# autowatering.net
KiCad netlist of a schematic drawn in Altium Designer
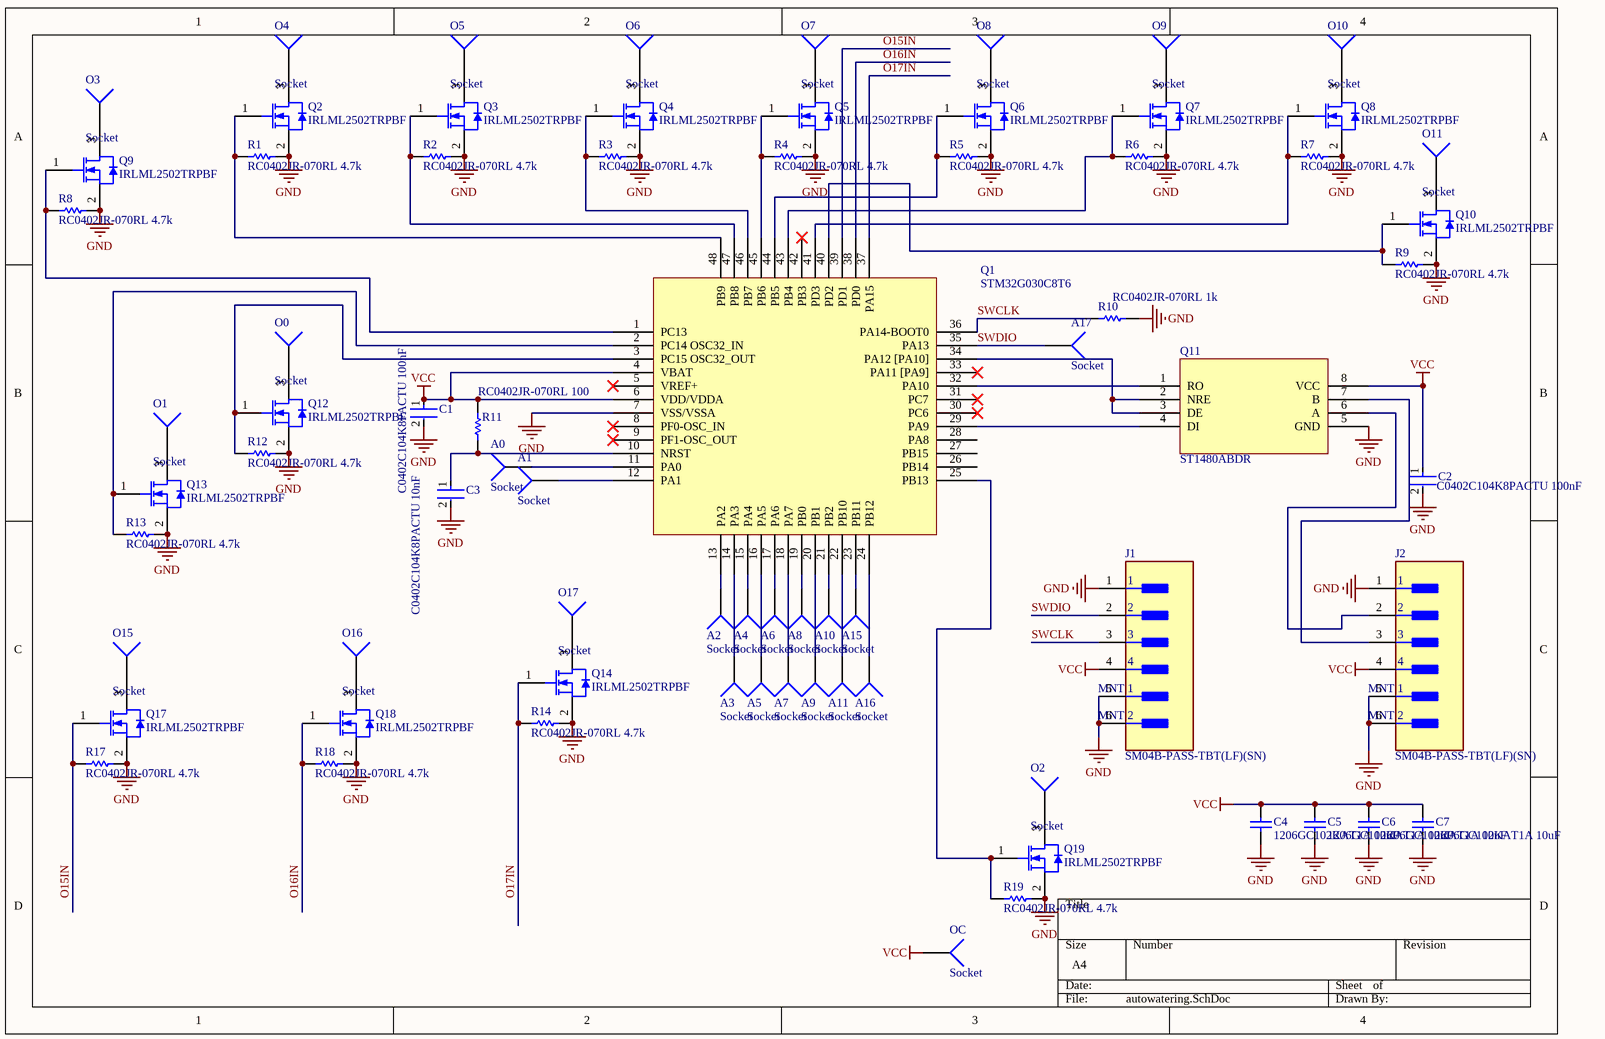
[diagram p0: autowatering.SchDoc]

(export (version "E")
  (design (tool "Eeschema 10.0.6"))
  (components
    (comp (ref "A0")
      (value "Socket")
      (footprint "PIN1")
      (fields (field (name "PUBLISHER") "Altium Limited"))
      (libsource (lib "Miscellaneous Connectors") (part "Socket"))
    )
    (comp (ref "A1")
      (value "Socket")
      (footprint "PIN1")
      (fields (field (name "PUBLISHER") "Altium Limited"))
      (libsource (lib "Miscellaneous Connectors") (part "Socket"))
    )
    (comp (ref "A2")
      (value "Socket")
      (footprint "PIN1")
      (fields (field (name "PUBLISHER") "Altium Limited"))
      (libsource (lib "Miscellaneous Connectors") (part "Socket"))
    )
    (comp (ref "A3")
      (value "Socket")
      (footprint "PIN1")
      (fields (field (name "PUBLISHER") "Altium Limited"))
      (libsource (lib "Miscellaneous Connectors") (part "Socket"))
    )
    (comp (ref "A4")
      (value "Socket")
      (footprint "PIN1")
      (fields (field (name "PUBLISHER") "Altium Limited"))
      (libsource (lib "Miscellaneous Connectors") (part "Socket"))
    )
    (comp (ref "A5")
      (value "Socket")
      (footprint "PIN1")
      (fields (field (name "PUBLISHER") "Altium Limited"))
      (libsource (lib "Miscellaneous Connectors") (part "Socket"))
    )
    (comp (ref "A6")
      (value "Socket")
      (footprint "PIN1")
      (fields (field (name "PUBLISHER") "Altium Limited"))
      (libsource (lib "Miscellaneous Connectors") (part "Socket"))
    )
    (comp (ref "A7")
      (value "Socket")
      (footprint "PIN1")
      (fields (field (name "PUBLISHER") "Altium Limited"))
      (libsource (lib "Miscellaneous Connectors") (part "Socket"))
    )
    (comp (ref "A8")
      (value "Socket")
      (footprint "PIN1")
      (fields (field (name "PUBLISHER") "Altium Limited"))
      (libsource (lib "Miscellaneous Connectors") (part "Socket"))
    )
    (comp (ref "A9")
      (value "Socket")
      (footprint "PIN1")
      (fields (field (name "PUBLISHER") "Altium Limited"))
      (libsource (lib "Miscellaneous Connectors") (part "Socket"))
    )
    (comp (ref "A10")
      (value "Socket")
      (footprint "PIN1")
      (fields (field (name "PUBLISHER") "Altium Limited"))
      (libsource (lib "Miscellaneous Connectors") (part "Socket"))
    )
    (comp (ref "A11")
      (value "Socket")
      (footprint "PIN1")
      (fields (field (name "PUBLISHER") "Altium Limited"))
      (libsource (lib "Miscellaneous Connectors") (part "Socket"))
    )
    (comp (ref "A15")
      (value "Socket")
      (footprint "PIN1")
      (fields (field (name "PUBLISHER") "Altium Limited"))
      (libsource (lib "Miscellaneous Connectors") (part "Socket"))
    )
    (comp (ref "A16")
      (value "Socket")
      (footprint "PIN1")
      (fields (field (name "PUBLISHER") "Altium Limited"))
      (libsource (lib "Miscellaneous Connectors") (part "Socket"))
    )
    (comp (ref "A17")
      (value "Socket")
      (footprint "PIN1")
      (fields (field (name "PUBLISHER") "Altium Limited"))
      (libsource (lib "Miscellaneous Connectors") (part "Socket"))
    )
    (comp (ref "C1")
      (value "C0402C104K8PACTU 100nF")
      (footprint "FP-C0402-BB-MFG")
      (description "CAP CER 0.1UF 10V X5R 0402")
      (fields (field (name "MANUFACTURER") "Kemet") (field (name "TOLERANCE") "0.1"))
      (libsource (lib "Altium Content Vault") (part "b4654b650e69147ec39a6b967a45e02"))
    )
    (comp (ref "C2")
      (value "C0402C104K8PACTU 100nF")
      (footprint "FP-C0402-BB-MFG")
      (description "CAP CER 0.1UF 10V X5R 0402")
      (fields (field (name "MANUFACTURER") "Kemet") (field (name "TOLERANCE") "0.1"))
      (libsource (lib "Altium Content Vault") (part "b4654b650e69147ec39a6b967a45e02"))
    )
    (comp (ref "C3")
      (value "C0402C104K8PACTU 10nF")
      (footprint "FP-C0402-BB-MFG")
      (description "CAP CER 0.1UF 10V X5R 0402")
      (fields (field (name "MANUFACTURER") "Kemet") (field (name "TOLERANCE") "0.1"))
      (libsource (lib "Altium Content Vault") (part "b4654b650e69147ec39a6b967a45e02"))
    )
    (comp (ref "C4")
      (value "1206GC102KAT1A 10uF")
      (footprint "AVX-1206-2_L")
      (description "Chip Capacitor, 1 nF, +/- 10%, -55 to 125 degC, 1206 (3216 Metric), RoHS, Tape and Reel")
      (fields (field (name "TOLERANCE") "10%") (field (name "PARTNUMBER") "1206GC102KAT1A"))
      (libsource (lib "Altium Content Vault") (part "CAP-NP-2"))
    )
    (comp (ref "C5")
      (value "1206GC102KAT1A 10uF")
      (footprint "AVX-1206-2_L")
      (description "Chip Capacitor, 1 nF, +/- 10%, -55 to 125 degC, 1206 (3216 Metric), RoHS, Tape and Reel")
      (fields (field (name "TOLERANCE") "10%") (field (name "PARTNUMBER") "1206GC102KAT1A"))
      (libsource (lib "Altium Content Vault") (part "CAP-NP-2"))
    )
    (comp (ref "C6")
      (value "1206GC102KAT1A 10uF")
      (footprint "AVX-1206-2_L")
      (description "Chip Capacitor, 1 nF, +/- 10%, -55 to 125 degC, 1206 (3216 Metric), RoHS, Tape and Reel")
      (fields (field (name "TOLERANCE") "10%") (field (name "PARTNUMBER") "1206GC102KAT1A"))
      (libsource (lib "Altium Content Vault") (part "CAP-NP-2"))
    )
    (comp (ref "C7")
      (value "1206GC102KAT1A 10uF")
      (footprint "AVX-1206-2_L")
      (description "Chip Capacitor, 1 nF, +/- 10%, -55 to 125 degC, 1206 (3216 Metric), RoHS, Tape and Reel")
      (fields (field (name "TOLERANCE") "10%") (field (name "PARTNUMBER") "1206GC102KAT1A"))
      (libsource (lib "Altium Content Vault") (part "CAP-NP-2"))
    )
    (comp (ref "J1")
      (value "SM04B-PASS-TBT(LF)(SN)")
      (footprint "FP-SM04B-PASS-TBT_LF_SN-MFG")
      (description "CONN HEADER SMD R/A 4POS 2MM")
      (fields
        (field (name "MANUFACTURER") "JST")
        (field (name "OCTOPART") "https://octopart.com/sm04b-pass-tbt%28lf%29%28sn%29-jst-3990422")
      )
      (libsource (lib "Altium Content Vault") (part "8e3688c4b118bffc0dd9b7401e414ba"))
    )
    (comp (ref "J2")
      (value "SM04B-PASS-TBT(LF)(SN)")
      (footprint "FP-SM04B-PASS-TBT_LF_SN-MFG")
      (description "CONN HEADER SMD R/A 4POS 2MM")
      (fields
        (field (name "MANUFACTURER") "JST")
        (field (name "OCTOPART") "https://octopart.com/sm04b-pass-tbt%28lf%29%28sn%29-jst-3990422")
      )
      (libsource (lib "Altium Content Vault") (part "8e3688c4b118bffc0dd9b7401e414ba"))
    )
    (comp (ref "O0")
      (value "Socket")
      (footprint "PIN1")
      (fields (field (name "PUBLISHER") "Altium Limited"))
      (libsource (lib "Miscellaneous Connectors") (part "Socket"))
    )
    (comp (ref "O1")
      (value "Socket")
      (footprint "PIN1")
      (fields (field (name "PUBLISHER") "Altium Limited"))
      (libsource (lib "Miscellaneous Connectors") (part "Socket"))
    )
    (comp (ref "O2")
      (value "Socket")
      (footprint "PIN1")
      (fields (field (name "PUBLISHER") "Altium Limited"))
      (libsource (lib "Miscellaneous Connectors") (part "Socket"))
    )
    (comp (ref "O3")
      (value "Socket")
      (footprint "PIN1")
      (fields (field (name "PUBLISHER") "Altium Limited"))
      (libsource (lib "Miscellaneous Connectors") (part "Socket"))
    )
    (comp (ref "O4")
      (value "Socket")
      (footprint "PIN1")
      (fields (field (name "PUBLISHER") "Altium Limited"))
      (libsource (lib "Miscellaneous Connectors") (part "Socket"))
    )
    (comp (ref "O5")
      (value "Socket")
      (footprint "PIN1")
      (fields (field (name "PUBLISHER") "Altium Limited"))
      (libsource (lib "Miscellaneous Connectors") (part "Socket"))
    )
    (comp (ref "O6")
      (value "Socket")
      (footprint "PIN1")
      (fields (field (name "PUBLISHER") "Altium Limited"))
      (libsource (lib "Miscellaneous Connectors") (part "Socket"))
    )
    (comp (ref "O7")
      (value "Socket")
      (footprint "PIN1")
      (fields (field (name "PUBLISHER") "Altium Limited"))
      (libsource (lib "Miscellaneous Connectors") (part "Socket"))
    )
    (comp (ref "O8")
      (value "Socket")
      (footprint "PIN1")
      (fields (field (name "PUBLISHER") "Altium Limited"))
      (libsource (lib "Miscellaneous Connectors") (part "Socket"))
    )
    (comp (ref "O9")
      (value "Socket")
      (footprint "PIN1")
      (fields (field (name "PUBLISHER") "Altium Limited"))
      (libsource (lib "Miscellaneous Connectors") (part "Socket"))
    )
    (comp (ref "O10")
      (value "Socket")
      (footprint "PIN1")
      (fields (field (name "PUBLISHER") "Altium Limited"))
      (libsource (lib "Miscellaneous Connectors") (part "Socket"))
    )
    (comp (ref "O11")
      (value "Socket")
      (footprint "PIN1")
      (fields (field (name "PUBLISHER") "Altium Limited"))
      (libsource (lib "Miscellaneous Connectors") (part "Socket"))
    )
    (comp (ref "O15")
      (value "Socket")
      (footprint "PIN1")
      (fields (field (name "PUBLISHER") "Altium Limited"))
      (libsource (lib "Miscellaneous Connectors") (part "Socket"))
    )
    (comp (ref "O16")
      (value "Socket")
      (footprint "PIN1")
      (fields (field (name "PUBLISHER") "Altium Limited"))
      (libsource (lib "Miscellaneous Connectors") (part "Socket"))
    )
    (comp (ref "O17")
      (value "Socket")
      (footprint "PIN1")
      (fields (field (name "PUBLISHER") "Altium Limited"))
      (libsource (lib "Miscellaneous Connectors") (part "Socket"))
    )
    (comp (ref "OC")
      (value "Socket")
      (footprint "PIN1")
      (fields (field (name "PUBLISHER") "Altium Limited"))
      (libsource (lib "Miscellaneous Connectors") (part "Socket"))
    )
    (comp (ref "Q1")
      (value "STM32G030C8T6")
      (footprint "LQFP-48")
      (libsource (lib "STM32G030C8T6") (part "STM32G030C8T6"))
    )
    (comp (ref "Q2")
      (value "IRLML2502TRPBF")
      (footprint "INTR-SOT-23-3_V")
      (description "N-Channel HEXFET(R) Power MOSFET, 20 V VDS, +/- 12 V VGS, 4.2 A, 3-Pin SOT23, RoHS, Tape and Reel")
      (fields (field (name "MANUFACTURER") "International Rectifier"))
      (libsource (lib "Altium Content Vault") (part "NEMOS-GSD-3"))
    )
    (comp (ref "Q3")
      (value "IRLML2502TRPBF")
      (footprint "INTR-SOT-23-3_V")
      (description "N-Channel HEXFET(R) Power MOSFET, 20 V VDS, +/- 12 V VGS, 4.2 A, 3-Pin SOT23, RoHS, Tape and Reel")
      (fields (field (name "MANUFACTURER") "International Rectifier"))
      (libsource (lib "Altium Content Vault") (part "NEMOS-GSD-3"))
    )
    (comp (ref "Q4")
      (value "IRLML2502TRPBF")
      (footprint "INTR-SOT-23-3_V")
      (description "N-Channel HEXFET(R) Power MOSFET, 20 V VDS, +/- 12 V VGS, 4.2 A, 3-Pin SOT23, RoHS, Tape and Reel")
      (fields (field (name "MANUFACTURER") "International Rectifier"))
      (libsource (lib "Altium Content Vault") (part "NEMOS-GSD-3"))
    )
    (comp (ref "Q5")
      (value "IRLML2502TRPBF")
      (footprint "INTR-SOT-23-3_V")
      (description "N-Channel HEXFET(R) Power MOSFET, 20 V VDS, +/- 12 V VGS, 4.2 A, 3-Pin SOT23, RoHS, Tape and Reel")
      (fields (field (name "MANUFACTURER") "International Rectifier"))
      (libsource (lib "Altium Content Vault") (part "NEMOS-GSD-3"))
    )
    (comp (ref "Q6")
      (value "IRLML2502TRPBF")
      (footprint "INTR-SOT-23-3_V")
      (description "N-Channel HEXFET(R) Power MOSFET, 20 V VDS, +/- 12 V VGS, 4.2 A, 3-Pin SOT23, RoHS, Tape and Reel")
      (fields (field (name "MANUFACTURER") "International Rectifier"))
      (libsource (lib "Altium Content Vault") (part "NEMOS-GSD-3"))
    )
    (comp (ref "Q7")
      (value "IRLML2502TRPBF")
      (footprint "INTR-SOT-23-3_V")
      (description "N-Channel HEXFET(R) Power MOSFET, 20 V VDS, +/- 12 V VGS, 4.2 A, 3-Pin SOT23, RoHS, Tape and Reel")
      (fields (field (name "MANUFACTURER") "International Rectifier"))
      (libsource (lib "Altium Content Vault") (part "NEMOS-GSD-3"))
    )
    (comp (ref "Q8")
      (value "IRLML2502TRPBF")
      (footprint "INTR-SOT-23-3_V")
      (description "N-Channel HEXFET(R) Power MOSFET, 20 V VDS, +/- 12 V VGS, 4.2 A, 3-Pin SOT23, RoHS, Tape and Reel")
      (fields (field (name "MANUFACTURER") "International Rectifier"))
      (libsource (lib "Altium Content Vault") (part "NEMOS-GSD-3"))
    )
    (comp (ref "Q9")
      (value "IRLML2502TRPBF")
      (footprint "INTR-SOT-23-3_V")
      (description "N-Channel HEXFET(R) Power MOSFET, 20 V VDS, +/- 12 V VGS, 4.2 A, 3-Pin SOT23, RoHS, Tape and Reel")
      (fields (field (name "MANUFACTURER") "International Rectifier"))
      (libsource (lib "Altium Content Vault") (part "NEMOS-GSD-3"))
    )
    (comp (ref "Q10")
      (value "IRLML2502TRPBF")
      (footprint "INTR-SOT-23-3_V")
      (description "N-Channel HEXFET(R) Power MOSFET, 20 V VDS, +/- 12 V VGS, 4.2 A, 3-Pin SOT23, RoHS, Tape and Reel")
      (fields (field (name "MANUFACTURER") "International Rectifier"))
      (libsource (lib "Altium Content Vault") (part "NEMOS-GSD-3"))
    )
    (comp (ref "Q11")
      (value "ST1480ABDR")
      (footprint "8S1_N")
      (libsource (lib "ST1480ABDR") (part "ST1480ABDR"))
    )
    (comp (ref "Q12")
      (value "IRLML2502TRPBF")
      (footprint "INTR-SOT-23-3_V")
      (description "N-Channel HEXFET(R) Power MOSFET, 20 V VDS, +/- 12 V VGS, 4.2 A, 3-Pin SOT23, RoHS, Tape and Reel")
      (fields (field (name "MANUFACTURER") "International Rectifier"))
      (libsource (lib "Altium Content Vault") (part "NEMOS-GSD-3"))
    )
    (comp (ref "Q13")
      (value "IRLML2502TRPBF")
      (footprint "INTR-SOT-23-3_V")
      (description "N-Channel HEXFET(R) Power MOSFET, 20 V VDS, +/- 12 V VGS, 4.2 A, 3-Pin SOT23, RoHS, Tape and Reel")
      (fields (field (name "MANUFACTURER") "International Rectifier"))
      (libsource (lib "Altium Content Vault") (part "NEMOS-GSD-3"))
    )
    (comp (ref "Q14")
      (value "IRLML2502TRPBF")
      (footprint "INTR-SOT-23-3_V")
      (description "N-Channel HEXFET(R) Power MOSFET, 20 V VDS, +/- 12 V VGS, 4.2 A, 3-Pin SOT23, RoHS, Tape and Reel")
      (fields (field (name "MANUFACTURER") "International Rectifier"))
      (libsource (lib "Altium Content Vault") (part "NEMOS-GSD-3"))
    )
    (comp (ref "Q17")
      (value "IRLML2502TRPBF")
      (footprint "INTR-SOT-23-3_V")
      (description "N-Channel HEXFET(R) Power MOSFET, 20 V VDS, +/- 12 V VGS, 4.2 A, 3-Pin SOT23, RoHS, Tape and Reel")
      (fields (field (name "MANUFACTURER") "International Rectifier"))
      (libsource (lib "Altium Content Vault") (part "NEMOS-GSD-3"))
    )
    (comp (ref "Q18")
      (value "IRLML2502TRPBF")
      (footprint "INTR-SOT-23-3_V")
      (description "N-Channel HEXFET(R) Power MOSFET, 20 V VDS, +/- 12 V VGS, 4.2 A, 3-Pin SOT23, RoHS, Tape and Reel")
      (fields (field (name "MANUFACTURER") "International Rectifier"))
      (libsource (lib "Altium Content Vault") (part "NEMOS-GSD-3"))
    )
    (comp (ref "Q19")
      (value "IRLML2502TRPBF")
      (footprint "INTR-SOT-23-3_V")
      (description "N-Channel HEXFET(R) Power MOSFET, 20 V VDS, +/- 12 V VGS, 4.2 A, 3-Pin SOT23, RoHS, Tape and Reel")
      (fields (field (name "MANUFACTURER") "International Rectifier"))
      (libsource (lib "Altium Content Vault") (part "NEMOS-GSD-3"))
    )
    (comp (ref "R1")
      (value "RC0402JR-070RL 4.7k")
      (footprint "RESC1005X40X25NL05T10")
      (fields (field (name "MANUFACTURER") "Yageo / Phycomp") (field (name "PART NUMBER") "RC0402JR-070RL"))
      (libsource (lib "Altium Content Vault") (part "RES"))
    )
    (comp (ref "R2")
      (value "RC0402JR-070RL 4.7k")
      (footprint "RESC1005X40X25NL05T10")
      (fields (field (name "MANUFACTURER") "Yageo / Phycomp") (field (name "PART NUMBER") "RC0402JR-070RL"))
      (libsource (lib "Altium Content Vault") (part "RES"))
    )
    (comp (ref "R3")
      (value "RC0402JR-070RL 4.7k")
      (footprint "RESC1005X40X25NL05T10")
      (fields (field (name "MANUFACTURER") "Yageo / Phycomp") (field (name "PART NUMBER") "RC0402JR-070RL"))
      (libsource (lib "Altium Content Vault") (part "RES"))
    )
    (comp (ref "R4")
      (value "RC0402JR-070RL 4.7k")
      (footprint "RESC1005X40X25NL05T10")
      (fields (field (name "MANUFACTURER") "Yageo / Phycomp") (field (name "PART NUMBER") "RC0402JR-070RL"))
      (libsource (lib "Altium Content Vault") (part "RES"))
    )
    (comp (ref "R5")
      (value "RC0402JR-070RL 4.7k")
      (footprint "RESC1005X40X25NL05T10")
      (fields (field (name "MANUFACTURER") "Yageo / Phycomp") (field (name "PART NUMBER") "RC0402JR-070RL"))
      (libsource (lib "Altium Content Vault") (part "RES"))
    )
    (comp (ref "R6")
      (value "RC0402JR-070RL 4.7k")
      (footprint "RESC1005X40X25NL05T10")
      (fields (field (name "MANUFACTURER") "Yageo / Phycomp") (field (name "PART NUMBER") "RC0402JR-070RL"))
      (libsource (lib "Altium Content Vault") (part "RES"))
    )
    (comp (ref "R7")
      (value "RC0402JR-070RL 4.7k")
      (footprint "RESC1005X40X25NL05T10")
      (fields (field (name "MANUFACTURER") "Yageo / Phycomp") (field (name "PART NUMBER") "RC0402JR-070RL"))
      (libsource (lib "Altium Content Vault") (part "RES"))
    )
    (comp (ref "R8")
      (value "RC0402JR-070RL 4.7k")
      (footprint "RESC1005X40X25NL05T10")
      (fields (field (name "MANUFACTURER") "Yageo / Phycomp") (field (name "PART NUMBER") "RC0402JR-070RL"))
      (libsource (lib "Altium Content Vault") (part "RES"))
    )
    (comp (ref "R9")
      (value "RC0402JR-070RL 4.7k")
      (footprint "RESC1005X40X25NL05T10")
      (fields (field (name "MANUFACTURER") "Yageo / Phycomp") (field (name "PART NUMBER") "RC0402JR-070RL"))
      (libsource (lib "Altium Content Vault") (part "RES"))
    )
    (comp (ref "R10")
      (value "RC0402JR-070RL 1k")
      (footprint "RESC1005X40X25NL05T10")
      (fields (field (name "MANUFACTURER") "Yageo / Phycomp") (field (name "PART NUMBER") "RC0402JR-070RL"))
      (libsource (lib "Altium Content Vault") (part "RES"))
    )
    (comp (ref "R11")
      (value "RC0402JR-070RL 100")
      (footprint "RESC1005X40X25NL05T10")
      (fields (field (name "MANUFACTURER") "Yageo / Phycomp") (field (name "PART NUMBER") "RC0402JR-070RL"))
      (libsource (lib "Altium Content Vault") (part "RES"))
    )
    (comp (ref "R12")
      (value "RC0402JR-070RL 4.7k")
      (footprint "RESC1005X40X25NL05T10")
      (fields (field (name "MANUFACTURER") "Yageo / Phycomp") (field (name "PART NUMBER") "RC0402JR-070RL"))
      (libsource (lib "Altium Content Vault") (part "RES"))
    )
    (comp (ref "R13")
      (value "RC0402JR-070RL 4.7k")
      (footprint "RESC1005X40X25NL05T10")
      (fields (field (name "MANUFACTURER") "Yageo / Phycomp") (field (name "PART NUMBER") "RC0402JR-070RL"))
      (libsource (lib "Altium Content Vault") (part "RES"))
    )
    (comp (ref "R14")
      (value "RC0402JR-070RL 4.7k")
      (footprint "RESC1005X40X25NL05T10")
      (fields (field (name "MANUFACTURER") "Yageo / Phycomp") (field (name "PART NUMBER") "RC0402JR-070RL"))
      (libsource (lib "Altium Content Vault") (part "RES"))
    )
    (comp (ref "R17")
      (value "RC0402JR-070RL 4.7k")
      (footprint "RESC1005X40X25NL05T10")
      (fields (field (name "MANUFACTURER") "Yageo / Phycomp") (field (name "PART NUMBER") "RC0402JR-070RL"))
      (libsource (lib "Altium Content Vault") (part "RES"))
    )
    (comp (ref "R18")
      (value "RC0402JR-070RL 4.7k")
      (footprint "RESC1005X40X25NL05T10")
      (fields (field (name "MANUFACTURER") "Yageo / Phycomp") (field (name "PART NUMBER") "RC0402JR-070RL"))
      (libsource (lib "Altium Content Vault") (part "RES"))
    )
    (comp (ref "R19")
      (value "RC0402JR-070RL 4.7k")
      (footprint "RESC1005X40X25NL05T10")
      (fields (field (name "MANUFACTURER") "Yageo / Phycomp") (field (name "PART NUMBER") "RC0402JR-070RL"))
      (libsource (lib "Altium Content Vault") (part "RES"))
    )
  )
  (nets
    (net (code "1") (name "/O15IN") (class "Default")
      (node (ref "Q1") (pin "39") (pinfunction "PD1_39") (pintype "passive"))
      (node (ref "Q17") (pin "1") (pinfunction "G_1") (pintype "passive"))
      (node (ref "R17") (pin "2") (pinfunction "2_2") (pintype "passive"))
    )
    (net (code "2") (name "/O16IN") (class "Default")
      (node (ref "Q1") (pin "38") (pinfunction "PD0_38") (pintype "passive"))
      (node (ref "Q18") (pin "1") (pinfunction "G_1") (pintype "passive"))
      (node (ref "R18") (pin "2") (pinfunction "2_2") (pintype "passive"))
    )
    (net (code "3") (name "/O17IN") (class "Default")
      (node (ref "Q1") (pin "37") (pinfunction "PA15_37") (pintype "passive"))
      (node (ref "Q14") (pin "1") (pinfunction "G_1") (pintype "passive"))
      (node (ref "R14") (pin "2") (pinfunction "2_2") (pintype "passive"))
    )
    (net (code "4") (name "/SWCLK") (class "Default")
      (node (ref "J1") (pin "3") (pinfunction "3_3") (pintype "passive"))
      (node (ref "Q1") (pin "36") (pinfunction "PA14-BOOT0_36") (pintype "passive"))
      (node (ref "R10") (pin "1") (pinfunction "1_1") (pintype "passive"))
    )
    (net (code "5") (name "/SWDIO") (class "Default")
      (node (ref "A17") (pin "1") (pinfunction "1_1") (pintype "passive"))
      (node (ref "J1") (pin "2") (pinfunction "2_2") (pintype "passive"))
      (node (ref "Q1") (pin "35") (pinfunction "PA13_35") (pintype "passive"))
    )
    (net (code "6") (name "GND") (class "Default")
      (node (ref "C1") (pin "2") (pinfunction "2_2") (pintype "passive"))
      (node (ref "C2") (pin "2") (pinfunction "2_2") (pintype "passive"))
      (node (ref "C3") (pin "2") (pinfunction "2_2") (pintype "passive"))
      (node (ref "C4") (pin "1") (pinfunction "1_1") (pintype "passive"))
      (node (ref "C5") (pin "1") (pinfunction "1_1") (pintype "passive"))
      (node (ref "C6") (pin "1") (pinfunction "1_1") (pintype "passive"))
      (node (ref "C7") (pin "1") (pinfunction "1_1") (pintype "passive"))
      (node (ref "J1") (pin "1") (pinfunction "1_1") (pintype "passive"))
      (node (ref "J1") (pin "5") (pinfunction "MNT_1_5") (pintype "passive"))
      (node (ref "J1") (pin "6") (pinfunction "MNT_2_6") (pintype "passive"))
      (node (ref "J2") (pin "1") (pinfunction "1_1") (pintype "passive"))
      (node (ref "J2") (pin "5") (pinfunction "MNT_1_5") (pintype "passive"))
      (node (ref "J2") (pin "6") (pinfunction "MNT_2_6") (pintype "passive"))
      (node (ref "Q1") (pin "7") (pinfunction "VSS/VSSA_7") (pintype "passive"))
      (node (ref "Q10") (pin "2") (pinfunction "S_2") (pintype "passive"))
      (node (ref "Q11") (pin "5") (pinfunction "GND_5") (pintype "passive"))
      (node (ref "Q12") (pin "2") (pinfunction "S_2") (pintype "passive"))
      (node (ref "Q13") (pin "2") (pinfunction "S_2") (pintype "passive"))
      (node (ref "Q14") (pin "2") (pinfunction "S_2") (pintype "passive"))
      (node (ref "Q17") (pin "2") (pinfunction "S_2") (pintype "passive"))
      (node (ref "Q18") (pin "2") (pinfunction "S_2") (pintype "passive"))
      (node (ref "Q19") (pin "2") (pinfunction "S_2") (pintype "passive"))
      (node (ref "Q2") (pin "2") (pinfunction "S_2") (pintype "passive"))
      (node (ref "Q3") (pin "2") (pinfunction "S_2") (pintype "passive"))
      (node (ref "Q4") (pin "2") (pinfunction "S_2") (pintype "passive"))
      (node (ref "Q5") (pin "2") (pinfunction "S_2") (pintype "passive"))
      (node (ref "Q6") (pin "2") (pinfunction "S_2") (pintype "passive"))
      (node (ref "Q7") (pin "2") (pinfunction "S_2") (pintype "passive"))
      (node (ref "Q8") (pin "2") (pinfunction "S_2") (pintype "passive"))
      (node (ref "Q9") (pin "2") (pinfunction "S_2") (pintype "passive"))
      (node (ref "R1") (pin "1") (pinfunction "1_1") (pintype "passive"))
      (node (ref "R10") (pin "2") (pinfunction "2_2") (pintype "passive"))
      (node (ref "R12") (pin "1") (pinfunction "1_1") (pintype "passive"))
      (node (ref "R13") (pin "1") (pinfunction "1_1") (pintype "passive"))
      (node (ref "R14") (pin "1") (pinfunction "1_1") (pintype "passive"))
      (node (ref "R17") (pin "1") (pinfunction "1_1") (pintype "passive"))
      (node (ref "R18") (pin "1") (pinfunction "1_1") (pintype "passive"))
      (node (ref "R19") (pin "1") (pinfunction "1_1") (pintype "passive"))
      (node (ref "R2") (pin "1") (pinfunction "1_1") (pintype "passive"))
      (node (ref "R3") (pin "1") (pinfunction "1_1") (pintype "passive"))
      (node (ref "R4") (pin "1") (pinfunction "1_1") (pintype "passive"))
      (node (ref "R5") (pin "1") (pinfunction "1_1") (pintype "passive"))
      (node (ref "R6") (pin "1") (pinfunction "1_1") (pintype "passive"))
      (node (ref "R7") (pin "1") (pinfunction "1_1") (pintype "passive"))
      (node (ref "R8") (pin "1") (pinfunction "1_1") (pintype "passive"))
      (node (ref "R9") (pin "1") (pinfunction "1_1") (pintype "passive"))
    )
    (net (code "7") (name "Net-(Q1-NRST)") (class "Default")
      (node (ref "C3") (pin "1") (pinfunction "1_1") (pintype "passive"))
      (node (ref "Q1") (pin "10") (pinfunction "NRST_10") (pintype "passive"))
      (node (ref "R11") (pin "1") (pinfunction "1_1") (pintype "passive"))
    )
    (net (code "8") (name "Net-(Q1-PA0)") (class "Default")
      (node (ref "A0") (pin "1") (pinfunction "1_1") (pintype "passive"))
      (node (ref "Q1") (pin "11") (pinfunction "PA0_11") (pintype "passive"))
    )
    (net (code "9") (name "Net-(Q1-PA1)") (class "Default")
      (node (ref "A1") (pin "1") (pinfunction "1_1") (pintype "passive"))
      (node (ref "Q1") (pin "12") (pinfunction "PA1_12") (pintype "passive"))
    )
    (net (code "10") (name "Net-(Q1-PA2)") (class "Default")
      (node (ref "A2") (pin "1") (pinfunction "1_1") (pintype "passive"))
      (node (ref "Q1") (pin "13") (pinfunction "PA2_13") (pintype "passive"))
    )
    (net (code "11") (name "Net-(Q1-PA3)") (class "Default")
      (node (ref "A3") (pin "1") (pinfunction "1_1") (pintype "passive"))
      (node (ref "Q1") (pin "14") (pinfunction "PA3_14") (pintype "passive"))
    )
    (net (code "12") (name "Net-(Q1-PA4)") (class "Default")
      (node (ref "A4") (pin "1") (pinfunction "1_1") (pintype "passive"))
      (node (ref "Q1") (pin "15") (pinfunction "PA4_15") (pintype "passive"))
    )
    (net (code "13") (name "Net-(Q1-PA5)") (class "Default")
      (node (ref "A5") (pin "1") (pinfunction "1_1") (pintype "passive"))
      (node (ref "Q1") (pin "16") (pinfunction "PA5_16") (pintype "passive"))
    )
    (net (code "14") (name "Net-(Q1-PA6)") (class "Default")
      (node (ref "A6") (pin "1") (pinfunction "1_1") (pintype "passive"))
      (node (ref "Q1") (pin "17") (pinfunction "PA6_17") (pintype "passive"))
    )
    (net (code "15") (name "Net-(Q1-PA7)") (class "Default")
      (node (ref "A7") (pin "1") (pinfunction "1_1") (pintype "passive"))
      (node (ref "Q1") (pin "18") (pinfunction "PA7_18") (pintype "passive"))
    )
    (net (code "16") (name "Net-(Q1-PA9)") (class "Default")
      (node (ref "Q1") (pin "29") (pinfunction "PA9_29") (pintype "passive"))
      (node (ref "Q11") (pin "4") (pinfunction "DI_4") (pintype "passive"))
    )
    (net (code "17") (name "Net-(Q1-PA10)") (class "Default")
      (node (ref "Q1") (pin "32") (pinfunction "PA10_32") (pintype "passive"))
      (node (ref "Q11") (pin "1") (pinfunction "RO_1") (pintype "passive"))
    )
    (net (code "18") (name "Net-(Q1-PA12_[PA10])") (class "Default")
      (node (ref "Q1") (pin "34") (pinfunction "PA12_[PA10]_34") (pintype "passive"))
      (node (ref "Q11") (pin "2") (pinfunction "NRE_2") (pintype "passive"))
      (node (ref "Q11") (pin "3") (pinfunction "DE_3") (pintype "passive"))
    )
    (net (code "19") (name "Net-(Q1-PB0)") (class "Default")
      (node (ref "A8") (pin "1") (pinfunction "1_1") (pintype "passive"))
      (node (ref "Q1") (pin "19") (pinfunction "PB0_19") (pintype "passive"))
    )
    (net (code "20") (name "Net-(Q1-PB1)") (class "Default")
      (node (ref "A9") (pin "1") (pinfunction "1_1") (pintype "passive"))
      (node (ref "Q1") (pin "20") (pinfunction "PB1_20") (pintype "passive"))
    )
    (net (code "21") (name "Net-(Q1-PB2)") (class "Default")
      (node (ref "A10") (pin "1") (pinfunction "1_1") (pintype "passive"))
      (node (ref "Q1") (pin "21") (pinfunction "PB2_21") (pintype "passive"))
    )
    (net (code "22") (name "Net-(Q1-PB4)") (class "Default")
      (node (ref "Q1") (pin "43") (pinfunction "PB4_43") (pintype "passive"))
      (node (ref "Q7") (pin "1") (pinfunction "G_1") (pintype "passive"))
      (node (ref "R6") (pin "2") (pinfunction "2_2") (pintype "passive"))
    )
    (net (code "23") (name "Net-(Q1-PB5)") (class "Default")
      (node (ref "Q1") (pin "44") (pinfunction "PB5_44") (pintype "passive"))
      (node (ref "Q6") (pin "1") (pinfunction "G_1") (pintype "passive"))
      (node (ref "R5") (pin "2") (pinfunction "2_2") (pintype "passive"))
    )
    (net (code "24") (name "Net-(Q1-PB6)") (class "Default")
      (node (ref "Q1") (pin "45") (pinfunction "PB6_45") (pintype "passive"))
      (node (ref "Q5") (pin "1") (pinfunction "G_1") (pintype "passive"))
      (node (ref "R4") (pin "2") (pinfunction "2_2") (pintype "passive"))
    )
    (net (code "25") (name "Net-(Q1-PB7)") (class "Default")
      (node (ref "Q1") (pin "46") (pinfunction "PB7_46") (pintype "passive"))
      (node (ref "Q4") (pin "1") (pinfunction "G_1") (pintype "passive"))
      (node (ref "R3") (pin "2") (pinfunction "2_2") (pintype "passive"))
    )
    (net (code "26") (name "Net-(Q1-PB8)") (class "Default")
      (node (ref "Q1") (pin "47") (pinfunction "PB8_47") (pintype "passive"))
      (node (ref "Q3") (pin "1") (pinfunction "G_1") (pintype "passive"))
      (node (ref "R2") (pin "2") (pinfunction "2_2") (pintype "passive"))
    )
    (net (code "27") (name "Net-(Q1-PB9)") (class "Default")
      (node (ref "Q1") (pin "48") (pinfunction "PB9_48") (pintype "passive"))
      (node (ref "Q2") (pin "1") (pinfunction "G_1") (pintype "passive"))
      (node (ref "R1") (pin "2") (pinfunction "2_2") (pintype "passive"))
    )
    (net (code "28") (name "Net-(Q1-PB10)") (class "Default")
      (node (ref "A11") (pin "1") (pinfunction "1_1") (pintype "passive"))
      (node (ref "Q1") (pin "22") (pinfunction "PB10_22") (pintype "passive"))
    )
    (net (code "29") (name "Net-(Q1-PB11)") (class "Default")
      (node (ref "A15") (pin "1") (pinfunction "1_1") (pintype "passive"))
      (node (ref "Q1") (pin "23") (pinfunction "PB11_23") (pintype "passive"))
    )
    (net (code "30") (name "Net-(Q1-PB12)") (class "Default")
      (node (ref "A16") (pin "1") (pinfunction "1_1") (pintype "passive"))
      (node (ref "Q1") (pin "24") (pinfunction "PB12_24") (pintype "passive"))
    )
    (net (code "31") (name "Net-(Q1-PB13)") (class "Default")
      (node (ref "Q1") (pin "25") (pinfunction "PB13_25") (pintype "passive"))
      (node (ref "Q19") (pin "1") (pinfunction "G_1") (pintype "passive"))
      (node (ref "R19") (pin "2") (pinfunction "2_2") (pintype "passive"))
    )
    (net (code "32") (name "Net-(Q1-PC13)") (class "Default")
      (node (ref "Q1") (pin "1") (pinfunction "PC13_1") (pintype "passive"))
      (node (ref "Q9") (pin "1") (pinfunction "G_1") (pintype "passive"))
      (node (ref "R8") (pin "2") (pinfunction "2_2") (pintype "passive"))
    )
    (net (code "33") (name "Net-(Q1-PC14_OSC32_IN)") (class "Default")
      (node (ref "Q1") (pin "2") (pinfunction "PC14_OSC32_IN_2") (pintype "passive"))
      (node (ref "Q13") (pin "1") (pinfunction "G_1") (pintype "passive"))
      (node (ref "R13") (pin "2") (pinfunction "2_2") (pintype "passive"))
    )
    (net (code "34") (name "Net-(Q1-PC15_OSC32_OUT)") (class "Default")
      (node (ref "Q1") (pin "3") (pinfunction "PC15_OSC32_OUT_3") (pintype "passive"))
      (node (ref "Q12") (pin "1") (pinfunction "G_1") (pintype "passive"))
      (node (ref "R12") (pin "2") (pinfunction "2_2") (pintype "passive"))
    )
    (net (code "35") (name "Net-(Q1-PD2)") (class "Default")
      (node (ref "Q1") (pin "40") (pinfunction "PD2_40") (pintype "passive"))
      (node (ref "Q10") (pin "1") (pinfunction "G_1") (pintype "passive"))
      (node (ref "R9") (pin "2") (pinfunction "2_2") (pintype "passive"))
    )
    (net (code "36") (name "Net-(Q1-PD3)") (class "Default")
      (node (ref "Q1") (pin "41") (pinfunction "PD3_41") (pintype "passive"))
      (node (ref "Q8") (pin "1") (pinfunction "G_1") (pintype "passive"))
      (node (ref "R7") (pin "2") (pinfunction "2_2") (pintype "passive"))
    )
    (net (code "37") (name "Net-(Q2-D)") (class "Default")
      (node (ref "O4") (pin "1") (pinfunction "1_1") (pintype "passive"))
      (node (ref "Q2") (pin "3") (pinfunction "D_3") (pintype "passive"))
    )
    (net (code "38") (name "Net-(Q3-D)") (class "Default")
      (node (ref "O5") (pin "1") (pinfunction "1_1") (pintype "passive"))
      (node (ref "Q3") (pin "3") (pinfunction "D_3") (pintype "passive"))
    )
    (net (code "39") (name "Net-(Q4-D)") (class "Default")
      (node (ref "O6") (pin "1") (pinfunction "1_1") (pintype "passive"))
      (node (ref "Q4") (pin "3") (pinfunction "D_3") (pintype "passive"))
    )
    (net (code "40") (name "Net-(Q5-D)") (class "Default")
      (node (ref "O7") (pin "1") (pinfunction "1_1") (pintype "passive"))
      (node (ref "Q5") (pin "3") (pinfunction "D_3") (pintype "passive"))
    )
    (net (code "41") (name "Net-(Q6-D)") (class "Default")
      (node (ref "O8") (pin "1") (pinfunction "1_1") (pintype "passive"))
      (node (ref "Q6") (pin "3") (pinfunction "D_3") (pintype "passive"))
    )
    (net (code "42") (name "Net-(Q7-D)") (class "Default")
      (node (ref "O9") (pin "1") (pinfunction "1_1") (pintype "passive"))
      (node (ref "Q7") (pin "3") (pinfunction "D_3") (pintype "passive"))
    )
    (net (code "43") (name "Net-(Q8-D)") (class "Default")
      (node (ref "O10") (pin "1") (pinfunction "1_1") (pintype "passive"))
      (node (ref "Q8") (pin "3") (pinfunction "D_3") (pintype "passive"))
    )
    (net (code "44") (name "Net-(Q9-D)") (class "Default")
      (node (ref "O3") (pin "1") (pinfunction "1_1") (pintype "passive"))
      (node (ref "Q9") (pin "3") (pinfunction "D_3") (pintype "passive"))
    )
    (net (code "45") (name "Net-(Q10-D)") (class "Default")
      (node (ref "O11") (pin "1") (pinfunction "1_1") (pintype "passive"))
      (node (ref "Q10") (pin "3") (pinfunction "D_3") (pintype "passive"))
    )
    (net (code "46") (name "Net-(Q11-A)") (class "Default")
      (node (ref "J2") (pin "2") (pinfunction "2_2") (pintype "passive"))
      (node (ref "Q11") (pin "6") (pinfunction "A_6") (pintype "passive"))
    )
    (net (code "47") (name "Net-(Q11-B)") (class "Default")
      (node (ref "J2") (pin "3") (pinfunction "3_3") (pintype "passive"))
      (node (ref "Q11") (pin "7") (pinfunction "B_7") (pintype "passive"))
    )
    (net (code "48") (name "Net-(Q12-D)") (class "Default")
      (node (ref "O0") (pin "1") (pinfunction "1_1") (pintype "passive"))
      (node (ref "Q12") (pin "3") (pinfunction "D_3") (pintype "passive"))
    )
    (net (code "49") (name "Net-(Q13-D)") (class "Default")
      (node (ref "O1") (pin "1") (pinfunction "1_1") (pintype "passive"))
      (node (ref "Q13") (pin "3") (pinfunction "D_3") (pintype "passive"))
    )
    (net (code "50") (name "Net-(Q14-D)") (class "Default")
      (node (ref "O17") (pin "1") (pinfunction "1_1") (pintype "passive"))
      (node (ref "Q14") (pin "3") (pinfunction "D_3") (pintype "passive"))
    )
    (net (code "51") (name "Net-(Q17-D)") (class "Default")
      (node (ref "O15") (pin "1") (pinfunction "1_1") (pintype "passive"))
      (node (ref "Q17") (pin "3") (pinfunction "D_3") (pintype "passive"))
    )
    (net (code "52") (name "Net-(Q18-D)") (class "Default")
      (node (ref "O16") (pin "1") (pinfunction "1_1") (pintype "passive"))
      (node (ref "Q18") (pin "3") (pinfunction "D_3") (pintype "passive"))
    )
    (net (code "53") (name "Net-(Q19-D)") (class "Default")
      (node (ref "O2") (pin "1") (pinfunction "1_1") (pintype "passive"))
      (node (ref "Q19") (pin "3") (pinfunction "D_3") (pintype "passive"))
    )
    (net (code "54") (name "VCC") (class "Default")
      (node (ref "C1") (pin "1") (pinfunction "1_1") (pintype "passive"))
      (node (ref "C2") (pin "1") (pinfunction "1_1") (pintype "passive"))
      (node (ref "C4") (pin "2") (pinfunction "2_2") (pintype "passive"))
      (node (ref "C5") (pin "2") (pinfunction "2_2") (pintype "passive"))
      (node (ref "C6") (pin "2") (pinfunction "2_2") (pintype "passive"))
      (node (ref "C7") (pin "2") (pinfunction "2_2") (pintype "passive"))
      (node (ref "J1") (pin "4") (pinfunction "4_4") (pintype "passive"))
      (node (ref "J2") (pin "4") (pinfunction "4_4") (pintype "passive"))
      (node (ref "OC") (pin "1") (pinfunction "1_1") (pintype "passive"))
      (node (ref "Q1") (pin "4") (pinfunction "VBAT_4") (pintype "passive"))
      (node (ref "Q1") (pin "6") (pinfunction "VDD/VDDA_6") (pintype "passive"))
      (node (ref "Q11") (pin "8") (pinfunction "VCC_8") (pintype "passive"))
      (node (ref "R11") (pin "2") (pinfunction "2_2") (pintype "passive"))
    )
    (net (code "55") (name "unconnected-(Q1-PA8-Pad28)") (class "Default")
      (node (ref "Q1") (pin "28") (pinfunction "PA8_28") (pintype "passive"))
    )
    (net (code "56") (name "unconnected-(Q1-PA11_[PA9]-Pad33)") (class "Default")
      (node (ref "Q1") (pin "33") (pinfunction "PA11_[PA9]_33") (pintype "passive+no_connect"))
    )
    (net (code "57") (name "unconnected-(Q1-PB3-Pad42)") (class "Default")
      (node (ref "Q1") (pin "42") (pinfunction "PB3_42") (pintype "passive+no_connect"))
    )
    (net (code "58") (name "unconnected-(Q1-PB14-Pad26)") (class "Default")
      (node (ref "Q1") (pin "26") (pinfunction "PB14_26") (pintype "passive"))
    )
    (net (code "59") (name "unconnected-(Q1-PB15-Pad27)") (class "Default")
      (node (ref "Q1") (pin "27") (pinfunction "PB15_27") (pintype "passive"))
    )
    (net (code "60") (name "unconnected-(Q1-PC6-Pad30)") (class "Default")
      (node (ref "Q1") (pin "30") (pinfunction "PC6_30") (pintype "passive+no_connect"))
    )
    (net (code "61") (name "unconnected-(Q1-PC7-Pad31)") (class "Default")
      (node (ref "Q1") (pin "31") (pinfunction "PC7_31") (pintype "passive+no_connect"))
    )
    (net (code "62") (name "unconnected-(Q1-PF0-OSC_IN-Pad8)") (class "Default")
      (node (ref "Q1") (pin "8") (pinfunction "PF0-OSC_IN_8") (pintype "passive+no_connect"))
    )
    (net (code "63") (name "unconnected-(Q1-PF1-OSC_OUT-Pad9)") (class "Default")
      (node (ref "Q1") (pin "9") (pinfunction "PF1-OSC_OUT_9") (pintype "passive+no_connect"))
    )
    (net (code "64") (name "unconnected-(Q1-VREF+-Pad5)") (class "Default")
      (node (ref "Q1") (pin "5") (pinfunction "VREF+_5") (pintype "passive+no_connect"))
    )
  )
)
